# 05.net
KiCad netlist of a schematic drawn in Altium Designer
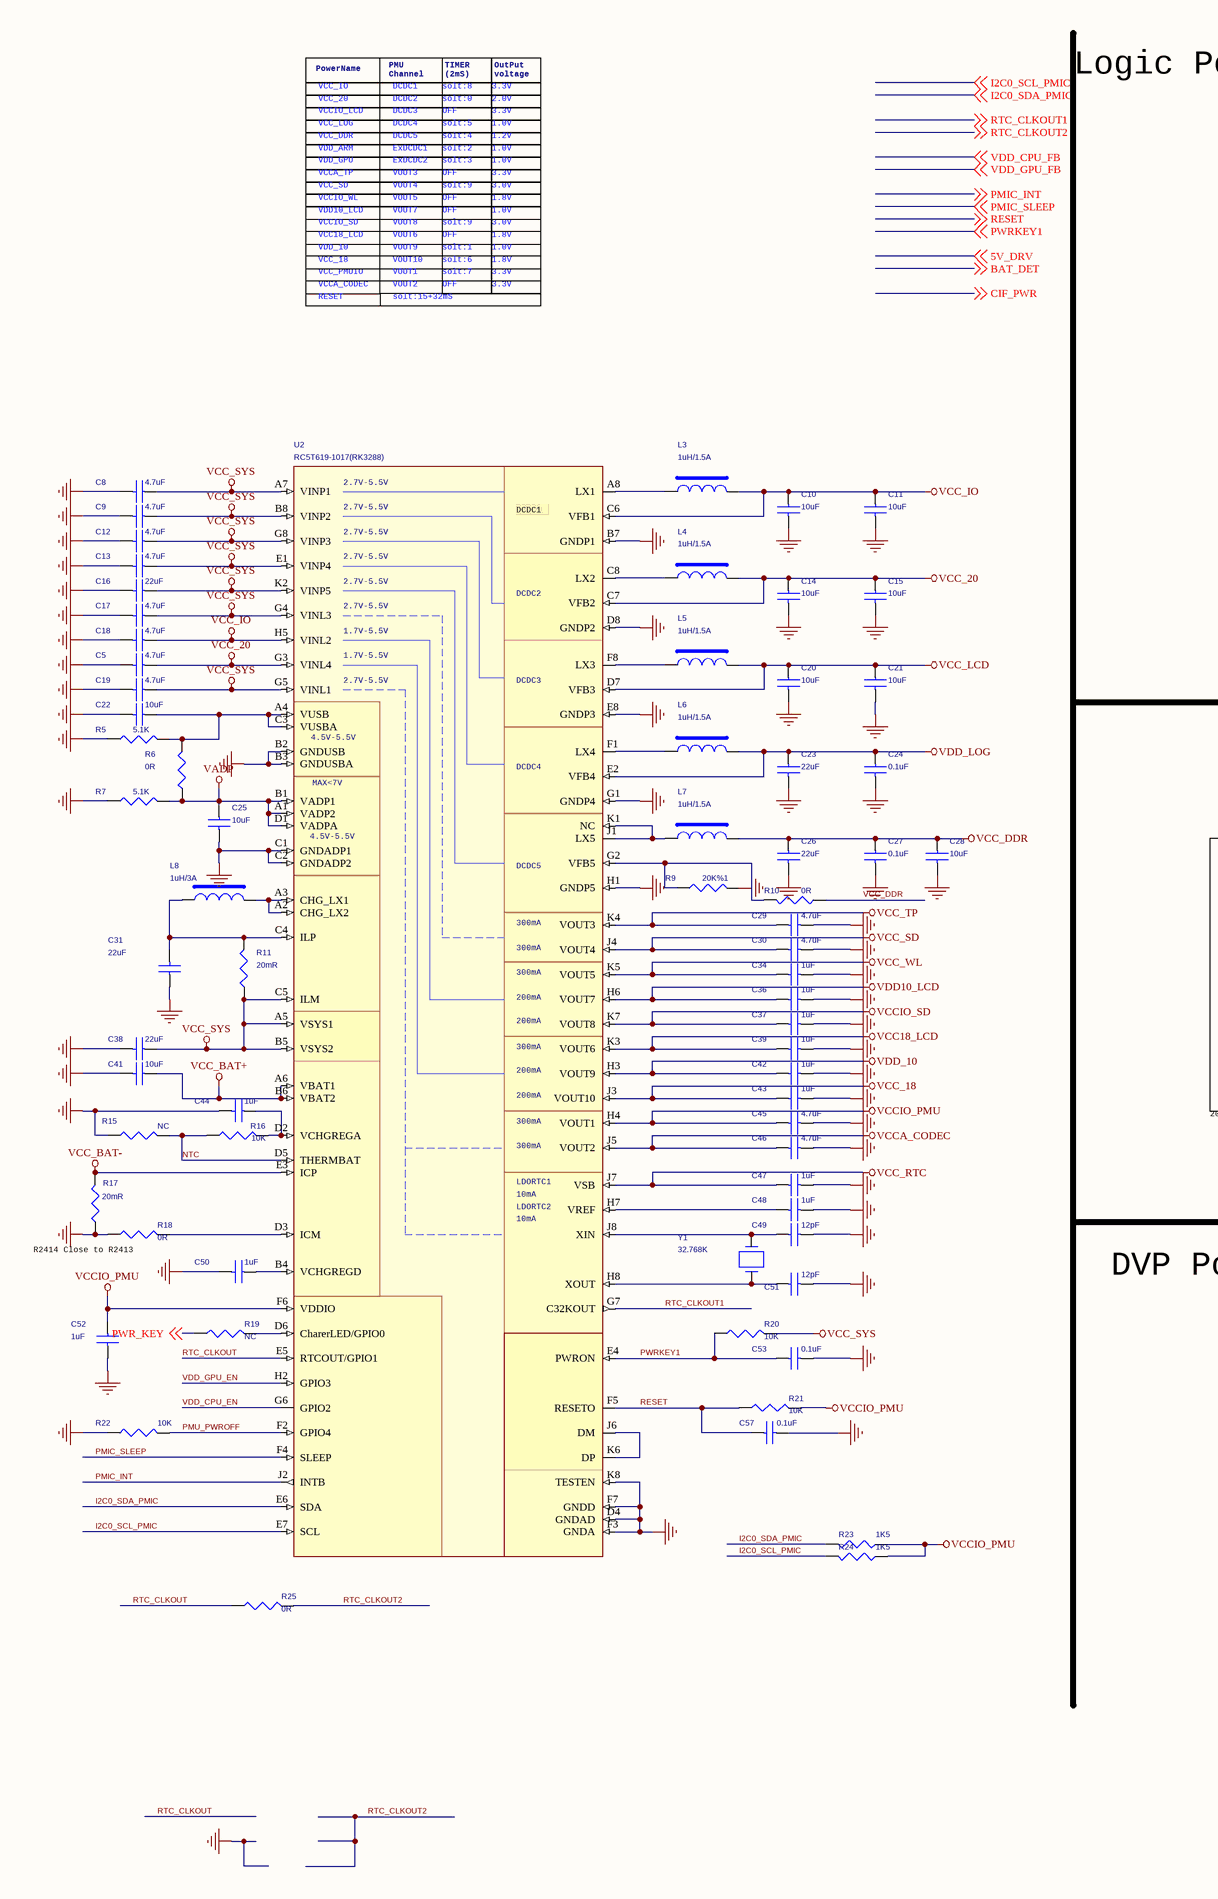
[diagram p0: 05.SchDoc, left]
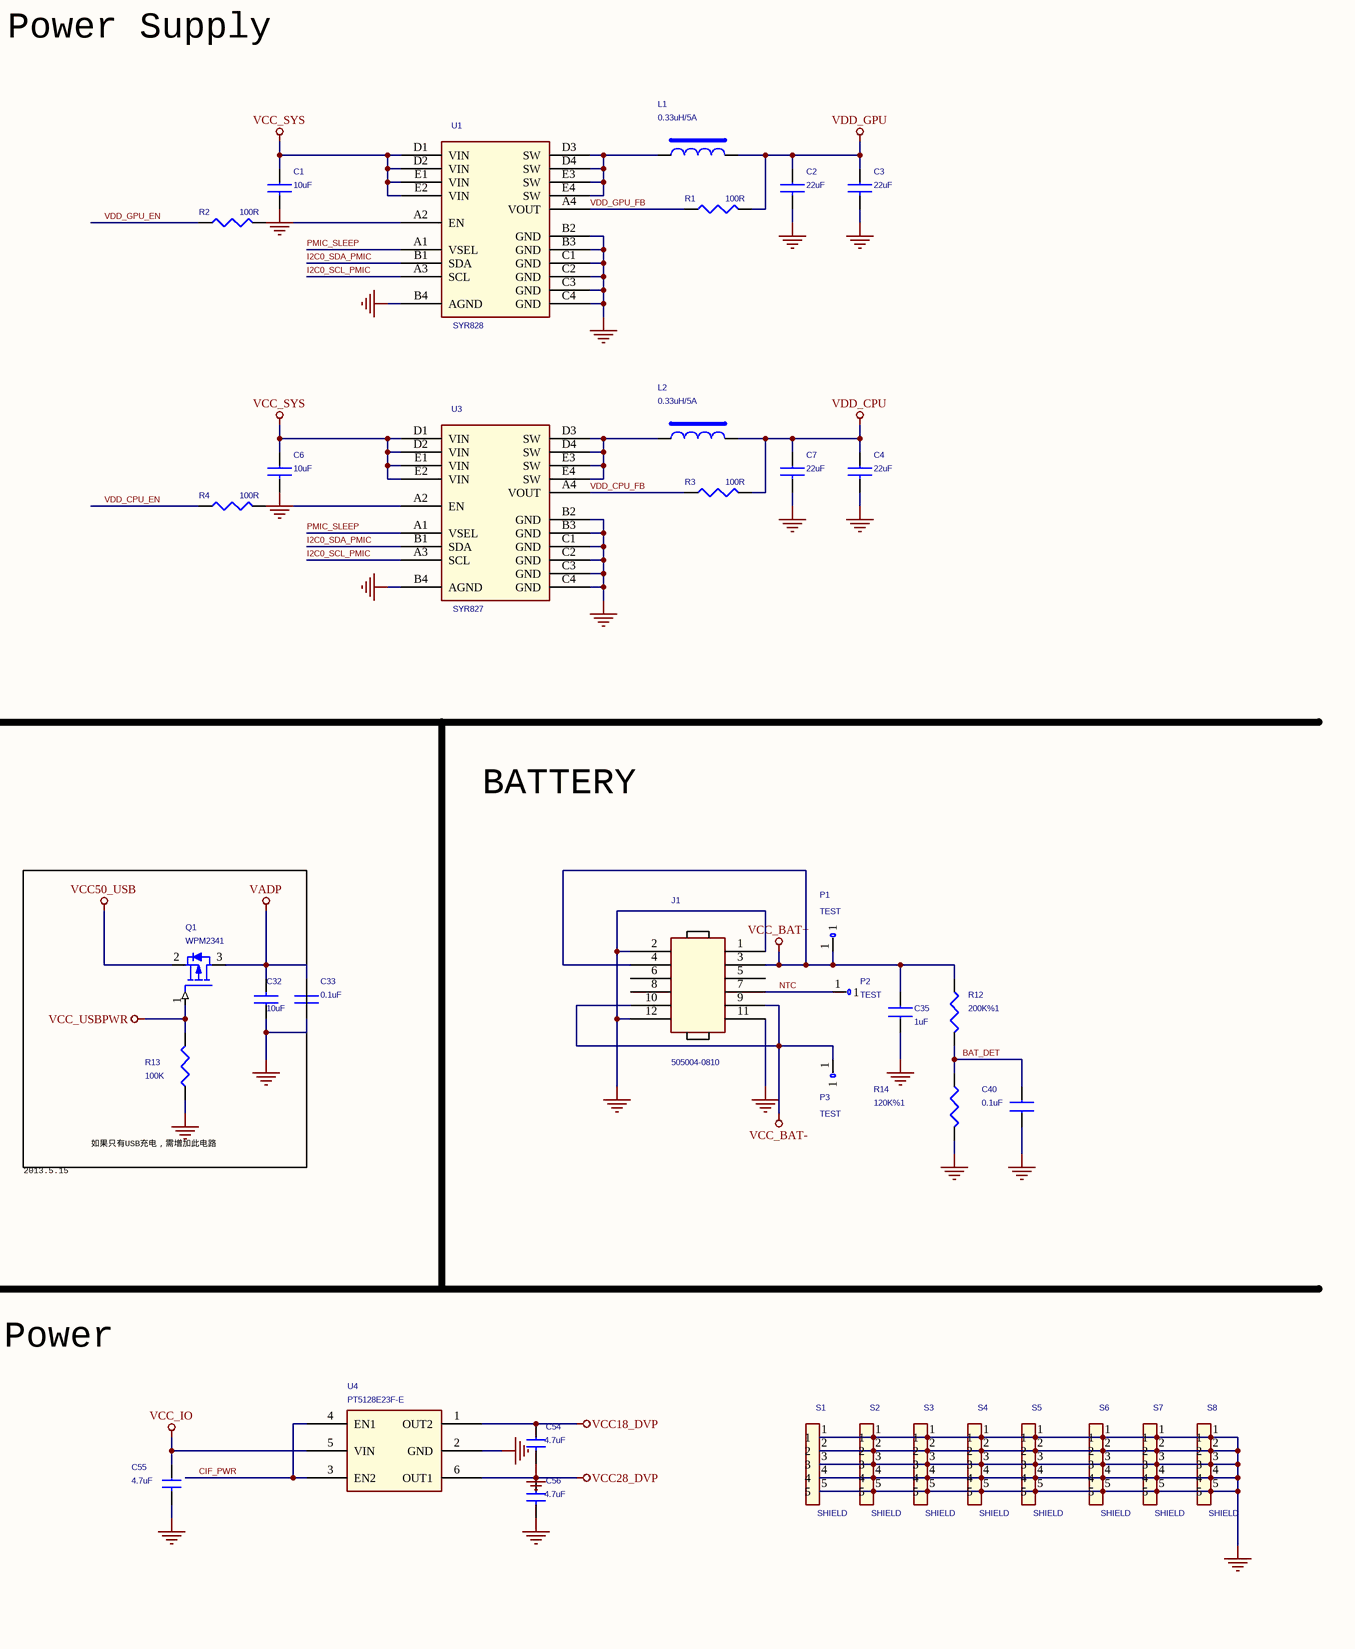
[diagram p1: 05.SchDoc, right]

(export (version "E")
  (design (tool "Eeschema 10.0.6"))
  (components
    (comp (ref "C1") (value "10uF") (footprint "C0603") (libsource (lib "*") (part "CAP NP_4")))
    (comp (ref "C2") (value "22uF") (footprint "C0805") (libsource (lib "*") (part "CAP NP_4")))
    (comp (ref "C3") (value "22uF") (footprint "C0805") (libsource (lib "*") (part "CAP NP_4")))
    (comp (ref "C4") (value "22uF") (footprint "C0805") (libsource (lib "*") (part "CAP NP_4")))
    (comp (ref "C5") (value "4.7uF") (footprint "C0603") (libsource (lib "*") (part "CAP NP_2")))
    (comp (ref "C6") (value "10uF") (footprint "C0603") (libsource (lib "*") (part "CAP NP_4")))
    (comp (ref "C7") (value "22uF") (footprint "C0805") (libsource (lib "*") (part "CAP NP_4")))
    (comp (ref "C8") (value "4.7uF") (footprint "C0603") (libsource (lib "*") (part "CAP NP_2")))
    (comp (ref "C9") (value "4.7uF") (footprint "C0603") (libsource (lib "*") (part "CAP NP_2")))
    (comp (ref "C10") (value "10uF") (footprint "C0603") (libsource (lib "*") (part "CAP NP_2")))
    (comp (ref "C11") (value "10uF") (footprint "C0603") (libsource (lib "*") (part "CAP NP_2")))
    (comp (ref "C12") (value "4.7uF") (footprint "C0603") (libsource (lib "*") (part "CAP NP_2")))
    (comp (ref "C13") (value "4.7uF") (footprint "C0603") (libsource (lib "*") (part "CAP NP_2")))
    (comp (ref "C14") (value "10uF") (footprint "C0603") (libsource (lib "*") (part "CAP NP_2")))
    (comp (ref "C15") (value "10uF") (footprint "C0603") (libsource (lib "*") (part "CAP NP_2")))
    (comp (ref "C16") (value "22uF") (footprint "C0805") (libsource (lib "*") (part "CAP NP_2")))
    (comp (ref "C17") (value "4.7uF") (footprint "C0603") (libsource (lib "*") (part "CAP NP_2")))
    (comp (ref "C18") (value "4.7uF") (footprint "C0603") (libsource (lib "*") (part "CAP NP_2")))
    (comp (ref "C19") (value "4.7uF") (footprint "C0603") (libsource (lib "*") (part "CAP NP_2")))
    (comp (ref "C20") (value "10uF") (footprint "C0603") (libsource (lib "*") (part "CAP NP_2")))
    (comp (ref "C21") (value "10uF") (footprint "C0603") (libsource (lib "*") (part "CAP NP_2")))
    (comp (ref "C22") (value "10uF") (footprint "C0603") (libsource (lib "*") (part "CAP NP_2")))
    (comp (ref "C23") (value "22uF") (footprint "C0805") (libsource (lib "*") (part "CAP NP_2")))
    (comp (ref "C24") (value "0.1uF") (footprint "c0402") (libsource (lib "*") (part "CAP NP_2")))
    (comp (ref "C25") (value "10uF") (footprint "C0603") (libsource (lib "*") (part "CAP NP_2")))
    (comp (ref "C26") (value "22uF") (footprint "C0805") (libsource (lib "*") (part "CAP NP_2")))
    (comp (ref "C27") (value "0.1uF") (footprint "c0402") (libsource (lib "*") (part "CAP NP_2")))
    (comp (ref "C28") (value "10uF") (footprint "C0603") (libsource (lib "*") (part "CAP NP_2")))
    (comp (ref "C29") (value "4.7uF") (footprint "C0603") (libsource (lib "*") (part "CAP NP_2")))
    (comp (ref "C30") (value "4.7uF") (footprint "C0603") (libsource (lib "*") (part "CAP NP_2")))
    (comp (ref "C31") (value "22uF") (footprint "C0805") (libsource (lib "*") (part "CAP NP_2")))
    (comp (ref "C32")
      (value "10uF")
      (footprint "C0603")
      (description "RoHS CHIP CAP 10uF +10/-10% X5R")
      (libsource (lib "*") (part "CAP NP_1"))
    )
    (comp (ref "C33")
      (value "0.1uF")
      (footprint "C0402")
      (description "RoHS CHIP CAP 0.1uF +10/-10% X7R")
      (libsource (lib "*") (part "CAP NP_Dup2"))
    )
    (comp (ref "C34") (value "1uF") (footprint "c0402") (libsource (lib "*") (part "CAP NP_2")))
    (comp (ref "C35")
      (value "1uF")
      (footprint "C0603")
      (description "RoHS CHIP CAP 1uF +10/-10% 16V X5R")
      (libsource (lib "*") (part "CAP NP_Dup3"))
    )
    (comp (ref "C36") (value "1uF") (footprint "c0402") (libsource (lib "*") (part "CAP NP_2")))
    (comp (ref "C37") (value "1uF") (footprint "c0402") (libsource (lib "*") (part "CAP NP_2")))
    (comp (ref "C38") (value "22uF") (footprint "C0805") (libsource (lib "*") (part "CAP NP_2")))
    (comp (ref "C39") (value "1uF") (footprint "c0402") (libsource (lib "*") (part "CAP NP_2")))
    (comp (ref "C40")
      (value "0.1uF")
      (footprint "C0603")
      (description "RoHS CHIP CAP 0.1uF +10/-10% X7R")
      (libsource (lib "*") (part "CAP NP_Dup3"))
    )
    (comp (ref "C41") (value "10uF") (footprint "C0603") (libsource (lib "*") (part "CAP NP_2")))
    (comp (ref "C42") (value "1uF") (footprint "c0402") (libsource (lib "*") (part "CAP NP_2")))
    (comp (ref "C43") (value "1uF") (footprint "c0402") (libsource (lib "*") (part "CAP NP_2")))
    (comp (ref "C44") (value "1uF") (footprint "c0402") (libsource (lib "*") (part "CAP NP_2")))
    (comp (ref "C45") (value "4.7uF") (footprint "C0603") (libsource (lib "*") (part "CAP NP_2")))
    (comp (ref "C46") (value "4.7uF") (footprint "C0603") (libsource (lib "*") (part "CAP NP_2")))
    (comp (ref "C47") (value "1uF") (footprint "c0402") (libsource (lib "*") (part "CAP NP_2")))
    (comp (ref "C48") (value "1uF") (footprint "c0402") (libsource (lib "*") (part "CAP NP_2")))
    (comp (ref "C49") (value "12pF") (footprint "c0402") (libsource (lib "*") (part "CAP NP_4")))
    (comp (ref "C50") (value "1uF") (footprint "c0402") (libsource (lib "*") (part "CAP NP_2")))
    (comp (ref "C51") (value "12pF") (footprint "c0402") (libsource (lib "*") (part "CAP NP_4")))
    (comp (ref "C52") (value "1uF") (footprint "c0402") (libsource (lib "*") (part "CAP NP_2")))
    (comp (ref "C53") (value "0.1uF") (footprint "c0402") (libsource (lib "*") (part "CAP NP_2")))
    (comp (ref "C54")
      (value "4.7uF")
      (footprint "C0603")
      (description "贴片电容")
      (libsource (lib "*") (part "SMALL CAP"))
    )
    (comp (ref "C55")
      (value "4.7uF")
      (footprint "C0603")
      (description "贴片电容")
      (libsource (lib "*") (part "SMALL CAP"))
    )
    (comp (ref "C56")
      (value "4.7uF")
      (footprint "C0603")
      (description "贴片电容")
      (libsource (lib "*") (part "SMALL CAP"))
    )
    (comp (ref "C57") (value "0.1uF") (footprint "c0402") (libsource (lib "*") (part "CAP NP_2")))
    (comp (ref "J1")
      (value "505004-0810")
      (footprint "505004-0810")
      (libsource (lib "*") (part "HEADER 6X2"))
    )
    (comp (ref "L1")
      (value "0.33uH/5A")
      (footprint "IND-4X4")
      (libsource (lib "*") (part "INDUCTORS OF FERRITE_Dup1"))
    )
    (comp (ref "L2")
      (value "0.33uH/5A")
      (footprint "IND-4X4")
      (libsource (lib "*") (part "INDUCTORS OF FERRITE_Dup1"))
    )
    (comp (ref "L3")
      (value "1uH/1.5A")
      (footprint "IND-3X3")
      (libsource (lib "*") (part "INDUCTORS OF FERRITE_Dup1"))
    )
    (comp (ref "L4")
      (value "1uH/1.5A")
      (footprint "IND-3X3")
      (libsource (lib "*") (part "INDUCTORS OF FERRITE_Dup1"))
    )
    (comp (ref "L5")
      (value "1uH/1.5A")
      (footprint "IND-3X3")
      (libsource (lib "*") (part "INDUCTORS OF FERRITE_Dup1"))
    )
    (comp (ref "L6")
      (value "1uH/1.5A")
      (footprint "IND-3X3")
      (libsource (lib "*") (part "INDUCTORS OF FERRITE_Dup1"))
    )
    (comp (ref "L7")
      (value "1uH/1.5A")
      (footprint "IND-3X3")
      (libsource (lib "*") (part "INDUCTORS OF FERRITE_Dup1"))
    )
    (comp (ref "L8")
      (value "1uH/3A")
      (footprint "IND-5X5")
      (libsource (lib "*") (part "INDUCTORS OF FERRITE_Dup1"))
    )
    (comp (ref "P1") (value "TEST") (footprint "TEST") (libsource (lib "*") (part "TEST_0")))
    (comp (ref "P2") (value "TEST") (footprint "TEST") (libsource (lib "*") (part "TEST_0")))
    (comp (ref "P3") (value "TEST") (footprint "TEST") (libsource (lib "*") (part "TEST_0")))
    (comp (ref "Q1")
      (value "WPM2341")
      (footprint "SOT23")
      (description "MOSFET-P,WPM2341 ,-20V,+/-8V,-2.8A,56m Ohm@Vgs=-2.5V,44m Ohm@Vgs=-4.5V,SOT23")
      (libsource (lib "*") (part "MOSFET P"))
    )
    (comp (ref "R1")
      (value "100R")
      (footprint "r0402")
      (description "RES,thick film,47KOhm,+/-5%,1/16W,SMD0402")
      (libsource (lib "*") (part "RESISTOR_1_Dup2"))
    )
    (comp (ref "R2")
      (value "100R")
      (footprint "r0402")
      (description "RES,thick film,47KOhm,+/-5%,1/16W,SMD0402")
      (libsource (lib "*") (part "RESISTOR_1_Dup2"))
    )
    (comp (ref "R3")
      (value "100R")
      (footprint "r0402")
      (description "RES,thick film,47KOhm,+/-5%,1/16W,SMD0402")
      (libsource (lib "*") (part "RESISTOR_1_Dup2"))
    )
    (comp (ref "R4")
      (value "100R")
      (footprint "r0402")
      (description "RES,thick film,47KOhm,+/-5%,1/16W,SMD0402")
      (libsource (lib "*") (part "RESISTOR_1_Dup2"))
    )
    (comp (ref "R5")
      (value "5.1K")
      (footprint "r0402")
      (description "贴片电阻")
      (libsource (lib "*") (part "RESISTOR_1"))
    )
    (comp (ref "R6")
      (value "0R")
      (footprint "R0402")
      (description "贴片电阻")
      (libsource (lib "*") (part "RESISTOR_1"))
    )
    (comp (ref "R7")
      (value "5.1K")
      (footprint "r0402")
      (description "贴片电阻")
      (libsource (lib "*") (part "RESISTOR_1"))
    )
    (comp (ref "R9")
      (value "20K%1")
      (footprint "r0402")
      (description "贴片电阻")
      (libsource (lib "*") (part "RESISTOR_1"))
    )
    (comp (ref "R10")
      (value "0R")
      (footprint "r0402")
      (description "贴片电阻")
      (libsource (lib "*") (part "RESISTOR_1"))
    )
    (comp (ref "R11")
      (value "20mR")
      (footprint "R1210")
      (description "贴片电阻")
      (libsource (lib "*") (part "RESISTOR_1"))
    )
    (comp (ref "R12")
      (value "200K%1")
      (footprint "r0402")
      (description "ROHS CHIP RES 100K 1/16W 1%")
      (libsource (lib "*") (part "RES 1B_Dup1"))
    )
    (comp (ref "R13")
      (value "100K")
      (footprint "r0402")
      (description "ROHS CHIP RES 10K 1/16W +/-5%")
      (libsource (lib "*") (part "RESISTOR"))
    )
    (comp (ref "R14")
      (value "120K%1")
      (footprint "r0402")
      (description "ROHS CHIP RES 100K 1/16W 1%")
      (libsource (lib "*") (part "RES 1B_Dup1"))
    )
    (comp (ref "R15")
      (value "NC")
      (footprint "r0402")
      (description "贴片电阻")
      (libsource (lib "*") (part "RESISTOR_1"))
    )
    (comp (ref "R16")
      (value "10K")
      (footprint "r0402")
      (description "贴片电阻")
      (libsource (lib "*") (part "RESISTOR_1"))
    )
    (comp (ref "R17")
      (value "20mR")
      (footprint "R1210")
      (description "贴片电阻")
      (libsource (lib "*") (part "RESISTOR_1"))
    )
    (comp (ref "R18")
      (value "0R")
      (footprint "r0402")
      (description "贴片电阻")
      (libsource (lib "*") (part "RESISTOR_1"))
    )
    (comp (ref "R19")
      (value "NC")
      (footprint "r0402")
      (description "贴片电阻")
      (libsource (lib "*") (part "RESISTOR_1"))
    )
    (comp (ref "R20")
      (value "10K")
      (footprint "r0402")
      (description "贴片电阻")
      (libsource (lib "*") (part "RESISTOR_1"))
    )
    (comp (ref "R21")
      (value "10K")
      (footprint "r0402")
      (description "贴片电阻")
      (libsource (lib "*") (part "RESISTOR_1"))
    )
    (comp (ref "R22")
      (value "10K")
      (footprint "r0402")
      (description "贴片电阻")
      (libsource (lib "*") (part "RESISTOR_1"))
    )
    (comp (ref "R23")
      (value "1K5")
      (footprint "r0402")
      (description "RES,thick film,47KOhm,+/-5%,1/16W,SMD0402")
      (libsource (lib "*") (part "RESISTOR_1_Dup2"))
    )
    (comp (ref "R24")
      (value "1K5")
      (footprint "r0402")
      (description "RES,thick film,47KOhm,+/-5%,1/16W,SMD0402")
      (libsource (lib "*") (part "RESISTOR_1_Dup2"))
    )
    (comp (ref "R25")
      (value "0R")
      (footprint "r0402")
      (description "贴片电阻")
      (libsource (lib "*") (part "RESISTOR_1"))
    )
    (comp (ref "S1") (value "SHIELD") (footprint "0_9MM_SHIELD") (libsource (lib "*") (part "SHIELD")))
    (comp (ref "S2") (value "SHIELD") (footprint "0_9MM_SHIELD") (libsource (lib "*") (part "SHIELD")))
    (comp (ref "S3") (value "SHIELD") (footprint "0_9MM_SHIELD") (libsource (lib "*") (part "SHIELD")))
    (comp (ref "S4") (value "SHIELD") (footprint "0_9MM_SHIELD") (libsource (lib "*") (part "SHIELD")))
    (comp (ref "S5") (value "SHIELD") (footprint "0_9MM_SHIELD") (libsource (lib "*") (part "SHIELD")))
    (comp (ref "S6") (value "SHIELD") (footprint "0_9MM_SHIELD") (libsource (lib "*") (part "SHIELD")))
    (comp (ref "S7") (value "SHIELD") (footprint "0_9MM_SHIELD") (libsource (lib "*") (part "SHIELD")))
    (comp (ref "S8") (value "SHIELD") (footprint "0_9MM_SHIELD") (libsource (lib "*") (part "SHIELD")))
    (comp (ref "U1") (value "SYR828") (footprint "WLCSP-20") (libsource (lib "*") (part "BB27_1")))
    (comp (ref "U2")
      (value "RC5T619-1017(RK3288)")
      (footprint "CSP0608-80")
      (libsource (lib "*") (part "5T619_2"))
    )
    (comp (ref "U3") (value "SYR827") (footprint "WLCSP-20") (libsource (lib "*") (part "BB27_1")))
    (comp (ref "U4") (value "PT5128E23F-E") (footprint "SOT26") (libsource (lib "*") (part "PT5127")))
    (comp (ref "Y1")
      (value "32.768K")
      (footprint "CRY-MC146")
      (description "Crystal,32.768KHz,+/-30ppm,12pF,MC146,-10°C ~ +60   °C")
      (libsource (lib "*") (part "CRYSTAL"))
    )
  )
  (nets
    (net (code "1") (name "/NTC") (class "Default")
      (node (ref "J1") (pin "7") (pinfunction "7_7") (pintype "passive"))
      (node (ref "P2") (pin "1") (pinfunction "1_1") (pintype "passive"))
      (node (ref "R15") (pin "1") (pinfunction "1_1") (pintype "passive"))
      (node (ref "R16") (pin "2") (pinfunction "2_2") (pintype "passive"))
      (node (ref "U2") (pin "D5") (pinfunction "THERMBAT_D5") (pintype "input"))
    )
    (net (code "2") (name "/PMU_PWROFF") (class "Default")
      (node (ref "R22") (pin "2") (pinfunction "2_2") (pintype "passive"))
      (node (ref "U2") (pin "F2") (pinfunction "GPIO4_F2") (pintype "input"))
    )
    (net (code "3") (name "/RTC_CLKOUT") (class "Default")
      (node (ref "R25") (pin "2") (pinfunction "2_2") (pintype "passive"))
      (node (ref "U2") (pin "E5") (pinfunction "RTCOUT/GPIO1_E5") (pintype "input"))
    )
    (net (code "4") (name "/VDD_CPU_EN") (class "Default")
      (node (ref "R4") (pin "2") (pinfunction "2_2") (pintype "passive"))
      (node (ref "U2") (pin "G6") (pinfunction "GPIO2_G6") (pintype "passive"))
    )
    (net (code "5") (name "/VDD_GPU_EN") (class "Default")
      (node (ref "R2") (pin "2") (pinfunction "2_2") (pintype "passive"))
      (node (ref "U2") (pin "H2") (pinfunction "GPIO3_H2") (pintype "input"))
    )
    (net (code "7") (name "BAT_DET") (class "Default")
      (node (ref "C40") (pin "2") (pinfunction "2_2") (pintype "passive"))
      (node (ref "R12") (pin "1") (pinfunction "1_1") (pintype "passive"))
      (node (ref "R14") (pin "2") (pinfunction "2_2") (pintype "passive"))
    )
    (net (code "8") (name "CIF_PWR") (class "Default")
      (node (ref "U4") (pin "3") (pinfunction "EN2_3") (pintype "passive"))
      (node (ref "U4") (pin "4") (pinfunction "EN1_4") (pintype "passive"))
    )
    (net (code "9") (name "GND") (class "Default")
      (node (ref "C1") (pin "2") (pinfunction "2_2") (pintype "passive"))
      (node (ref "C10") (pin "2") (pinfunction "2_2") (pintype "passive"))
      (node (ref "C11") (pin "2") (pinfunction "2_2") (pintype "passive"))
      (node (ref "C12") (pin "2") (pinfunction "2_2") (pintype "passive"))
      (node (ref "C13") (pin "2") (pinfunction "2_2") (pintype "passive"))
      (node (ref "C14") (pin "2") (pinfunction "2_2") (pintype "passive"))
      (node (ref "C15") (pin "2") (pinfunction "2_2") (pintype "passive"))
      (node (ref "C16") (pin "2") (pinfunction "2_2") (pintype "passive"))
      (node (ref "C17") (pin "2") (pinfunction "2_2") (pintype "passive"))
      (node (ref "C18") (pin "2") (pinfunction "2_2") (pintype "passive"))
      (node (ref "C19") (pin "2") (pinfunction "2_2") (pintype "passive"))
      (node (ref "C2") (pin "2") (pinfunction "2_2") (pintype "passive"))
      (node (ref "C20") (pin "2") (pinfunction "2_2") (pintype "passive"))
      (node (ref "C21") (pin "2") (pinfunction "2_2") (pintype "passive"))
      (node (ref "C22") (pin "2") (pinfunction "2_2") (pintype "passive"))
      (node (ref "C23") (pin "2") (pinfunction "2_2") (pintype "passive"))
      (node (ref "C24") (pin "2") (pinfunction "2_2") (pintype "passive"))
      (node (ref "C25") (pin "2") (pinfunction "2_2") (pintype "passive"))
      (node (ref "C26") (pin "2") (pinfunction "2_2") (pintype "passive"))
      (node (ref "C27") (pin "2") (pinfunction "2_2") (pintype "passive"))
      (node (ref "C28") (pin "2") (pinfunction "2_2") (pintype "passive"))
      (node (ref "C29") (pin "2") (pinfunction "2_2") (pintype "passive"))
      (node (ref "C3") (pin "2") (pinfunction "2_2") (pintype "passive"))
      (node (ref "C30") (pin "2") (pinfunction "2_2") (pintype "passive"))
      (node (ref "C31") (pin "1") (pinfunction "1_1") (pintype "passive"))
      (node (ref "C32") (pin "1") (pinfunction "1_1") (pintype "passive"))
      (node (ref "C33") (pin "1") (pinfunction "1_1") (pintype "passive"))
      (node (ref "C34") (pin "2") (pinfunction "2_2") (pintype "passive"))
      (node (ref "C35") (pin "1") (pinfunction "1_1") (pintype "passive"))
      (node (ref "C36") (pin "2") (pinfunction "2_2") (pintype "passive"))
      (node (ref "C37") (pin "2") (pinfunction "2_2") (pintype "passive"))
      (node (ref "C38") (pin "2") (pinfunction "2_2") (pintype "passive"))
      (node (ref "C39") (pin "2") (pinfunction "2_2") (pintype "passive"))
      (node (ref "C4") (pin "2") (pinfunction "2_2") (pintype "passive"))
      (node (ref "C40") (pin "1") (pinfunction "1_1") (pintype "passive"))
      (node (ref "C41") (pin "2") (pinfunction "2_2") (pintype "passive"))
      (node (ref "C42") (pin "2") (pinfunction "2_2") (pintype "passive"))
      (node (ref "C43") (pin "2") (pinfunction "2_2") (pintype "passive"))
      (node (ref "C44") (pin "2") (pinfunction "2_2") (pintype "passive"))
      (node (ref "C45") (pin "2") (pinfunction "2_2") (pintype "passive"))
      (node (ref "C46") (pin "2") (pinfunction "2_2") (pintype "passive"))
      (node (ref "C47") (pin "2") (pinfunction "2_2") (pintype "passive"))
      (node (ref "C48") (pin "2") (pinfunction "2_2") (pintype "passive"))
      (node (ref "C49") (pin "2") (pinfunction "2_2") (pintype "passive"))
      (node (ref "C5") (pin "2") (pinfunction "2_2") (pintype "passive"))
      (node (ref "C50") (pin "2") (pinfunction "2_2") (pintype "passive"))
      (node (ref "C51") (pin "2") (pinfunction "2_2") (pintype "passive"))
      (node (ref "C52") (pin "2") (pinfunction "2_2") (pintype "passive"))
      (node (ref "C53") (pin "2") (pinfunction "2_2") (pintype "passive"))
      (node (ref "C54") (pin "2") (pinfunction "2_2") (pintype "passive"))
      (node (ref "C55") (pin "2") (pinfunction "2_2") (pintype "passive"))
      (node (ref "C56") (pin "2") (pinfunction "2_2") (pintype "passive"))
      (node (ref "C57") (pin "2") (pinfunction "2_2") (pintype "passive"))
      (node (ref "C6") (pin "2") (pinfunction "2_2") (pintype "passive"))
      (node (ref "C7") (pin "2") (pinfunction "2_2") (pintype "passive"))
      (node (ref "C8") (pin "2") (pinfunction "2_2") (pintype "passive"))
      (node (ref "C9") (pin "2") (pinfunction "2_2") (pintype "passive"))
      (node (ref "J1") (pin "1") (pinfunction "1_1") (pintype "passive"))
      (node (ref "J1") (pin "11") (pinfunction "11_11") (pintype "passive"))
      (node (ref "J1") (pin "12") (pinfunction "12_12") (pintype "passive"))
      (node (ref "J1") (pin "2") (pinfunction "2_2") (pintype "passive"))
      (node (ref "R13") (pin "1") (pinfunction "1_1") (pintype "passive"))
      (node (ref "R14") (pin "1") (pinfunction "1_1") (pintype "passive"))
      (node (ref "R15") (pin "2") (pinfunction "2_2") (pintype "passive"))
      (node (ref "R17") (pin "1") (pinfunction "1_1") (pintype "passive"))
      (node (ref "R18") (pin "2") (pinfunction "2_2") (pintype "passive"))
      (node (ref "R22") (pin "1") (pinfunction "1_1") (pintype "passive"))
      (node (ref "R5") (pin "1") (pinfunction "1_1") (pintype "passive"))
      (node (ref "R7") (pin "1") (pinfunction "1_1") (pintype "passive"))
      (node (ref "R9") (pin "2") (pinfunction "2_2") (pintype "passive"))
      (node (ref "S1") (pin "1") (pinfunction "1_1") (pintype "passive"))
      (node (ref "S1") (pin "2") (pinfunction "2_2") (pintype "passive"))
      (node (ref "S1") (pin "3") (pinfunction "3_3") (pintype "passive"))
      (node (ref "S1") (pin "4") (pinfunction "4_4") (pintype "passive"))
      (node (ref "S1") (pin "5") (pinfunction "5_5") (pintype "passive"))
      (node (ref "S2") (pin "1") (pinfunction "1_1") (pintype "passive"))
      (node (ref "S2") (pin "2") (pinfunction "2_2") (pintype "passive"))
      (node (ref "S2") (pin "3") (pinfunction "3_3") (pintype "passive"))
      (node (ref "S2") (pin "4") (pinfunction "4_4") (pintype "passive"))
      (node (ref "S2") (pin "5") (pinfunction "5_5") (pintype "passive"))
      (node (ref "S3") (pin "1") (pinfunction "1_1") (pintype "passive"))
      (node (ref "S3") (pin "2") (pinfunction "2_2") (pintype "passive"))
      (node (ref "S3") (pin "3") (pinfunction "3_3") (pintype "passive"))
      (node (ref "S3") (pin "4") (pinfunction "4_4") (pintype "passive"))
      (node (ref "S3") (pin "5") (pinfunction "5_5") (pintype "passive"))
      (node (ref "S4") (pin "1") (pinfunction "1_1") (pintype "passive"))
      (node (ref "S4") (pin "2") (pinfunction "2_2") (pintype "passive"))
      (node (ref "S4") (pin "3") (pinfunction "3_3") (pintype "passive"))
      (node (ref "S4") (pin "4") (pinfunction "4_4") (pintype "passive"))
      (node (ref "S4") (pin "5") (pinfunction "5_5") (pintype "passive"))
      (node (ref "S5") (pin "1") (pinfunction "1_1") (pintype "passive"))
      (node (ref "S5") (pin "2") (pinfunction "2_2") (pintype "passive"))
      (node (ref "S5") (pin "3") (pinfunction "3_3") (pintype "passive"))
      (node (ref "S5") (pin "4") (pinfunction "4_4") (pintype "passive"))
      (node (ref "S5") (pin "5") (pinfunction "5_5") (pintype "passive"))
      (node (ref "S6") (pin "1") (pinfunction "1_1") (pintype "passive"))
      (node (ref "S6") (pin "2") (pinfunction "2_2") (pintype "passive"))
      (node (ref "S6") (pin "3") (pinfunction "3_3") (pintype "passive"))
      (node (ref "S6") (pin "4") (pinfunction "4_4") (pintype "passive"))
      (node (ref "S6") (pin "5") (pinfunction "5_5") (pintype "passive"))
      (node (ref "S7") (pin "1") (pinfunction "1_1") (pintype "passive"))
      (node (ref "S7") (pin "2") (pinfunction "2_2") (pintype "passive"))
      (node (ref "S7") (pin "3") (pinfunction "3_3") (pintype "passive"))
      (node (ref "S7") (pin "4") (pinfunction "4_4") (pintype "passive"))
      (node (ref "S7") (pin "5") (pinfunction "5_5") (pintype "passive"))
      (node (ref "S8") (pin "1") (pinfunction "1_1") (pintype "passive"))
      (node (ref "S8") (pin "2") (pinfunction "2_2") (pintype "passive"))
      (node (ref "S8") (pin "3") (pinfunction "3_3") (pintype "passive"))
      (node (ref "S8") (pin "4") (pinfunction "4_4") (pintype "passive"))
      (node (ref "S8") (pin "5") (pinfunction "5_5") (pintype "passive"))
      (node (ref "U1") (pin "B2") (pinfunction "GND_B2") (pintype "power_in"))
      (node (ref "U1") (pin "B3") (pinfunction "GND_B3") (pintype "power_in"))
      (node (ref "U1") (pin "B4") (pinfunction "AGND_B4") (pintype "passive"))
      (node (ref "U1") (pin "C1") (pinfunction "GND_C1") (pintype "power_in"))
      (node (ref "U1") (pin "C2") (pinfunction "GND_C2") (pintype "power_in"))
      (node (ref "U1") (pin "C3") (pinfunction "GND_C3") (pintype "power_in"))
      (node (ref "U1") (pin "C4") (pinfunction "GND_C4") (pintype "power_in"))
      (node (ref "U2") (pin "B2") (pinfunction "GNDUSB_B2") (pintype "input"))
      (node (ref "U2") (pin "B3") (pinfunction "GNDUSBA_B3") (pintype "input"))
      (node (ref "U2") (pin "B7") (pinfunction "GNDP1_B7") (pintype "input"))
      (node (ref "U2") (pin "C1") (pinfunction "GNDADP1_C1") (pintype "input"))
      (node (ref "U2") (pin "C2") (pinfunction "GNDADP2_C2") (pintype "input"))
      (node (ref "U2") (pin "D4") (pinfunction "GNDAD_D4") (pintype "input"))
      (node (ref "U2") (pin "D8") (pinfunction "GNDP2_D8") (pintype "input"))
      (node (ref "U2") (pin "E8") (pinfunction "GNDP3_E8") (pintype "input"))
      (node (ref "U2") (pin "F3") (pinfunction "GNDA_F3") (pintype "input"))
      (node (ref "U2") (pin "F7") (pinfunction "GNDD_F7") (pintype "input"))
      (node (ref "U2") (pin "G1") (pinfunction "GNDP4_G1") (pintype "input"))
      (node (ref "U2") (pin "H1") (pinfunction "GNDP5_H1") (pintype "input"))
      (node (ref "U2") (pin "K8") (pinfunction "TESTEN_K8") (pintype "input"))
      (node (ref "U3") (pin "B2") (pinfunction "GND_B2") (pintype "power_in"))
      (node (ref "U3") (pin "B3") (pinfunction "GND_B3") (pintype "power_in"))
      (node (ref "U3") (pin "B4") (pinfunction "AGND_B4") (pintype "passive"))
      (node (ref "U3") (pin "C1") (pinfunction "GND_C1") (pintype "power_in"))
      (node (ref "U3") (pin "C2") (pinfunction "GND_C2") (pintype "power_in"))
      (node (ref "U3") (pin "C3") (pinfunction "GND_C3") (pintype "power_in"))
      (node (ref "U3") (pin "C4") (pinfunction "GND_C4") (pintype "power_in"))
      (node (ref "U4") (pin "2") (pinfunction "GND_2") (pintype "passive"))
    )
    (net (code "10") (name "I2C0_SCL_PMIC") (class "Default")
      (node (ref "R24") (pin "1") (pinfunction "1_1") (pintype "passive"))
      (node (ref "U1") (pin "A3") (pinfunction "SCL_A3") (pintype "passive"))
      (node (ref "U2") (pin "E7") (pinfunction "SCL_E7") (pintype "input"))
      (node (ref "U3") (pin "A3") (pinfunction "SCL_A3") (pintype "passive"))
    )
    (net (code "11") (name "I2C0_SDA_PMIC") (class "Default")
      (node (ref "R23") (pin "1") (pinfunction "1_1") (pintype "passive"))
      (node (ref "U1") (pin "B1") (pinfunction "SDA_B1") (pintype "passive"))
      (node (ref "U2") (pin "E6") (pinfunction "SDA_E6") (pintype "input"))
      (node (ref "U3") (pin "B1") (pinfunction "SDA_B1") (pintype "passive"))
    )
    (net (code "12") (name "Net-(L1-Pad1)") (class "Default")
      (node (ref "L1") (pin "1") (pinfunction "1_1") (pintype "passive"))
      (node (ref "U1") (pin "D3") (pinfunction "SW_D3") (pintype "power_in"))
      (node (ref "U1") (pin "D4") (pinfunction "SW_D4") (pintype "power_in"))
      (node (ref "U1") (pin "E3") (pinfunction "SW_E3") (pintype "power_in"))
      (node (ref "U1") (pin "E4") (pinfunction "SW_E4") (pintype "power_in"))
    )
    (net (code "13") (name "Net-(L2-Pad1)") (class "Default")
      (node (ref "L2") (pin "1") (pinfunction "1_1") (pintype "passive"))
      (node (ref "U3") (pin "D3") (pinfunction "SW_D3") (pintype "power_in"))
      (node (ref "U3") (pin "D4") (pinfunction "SW_D4") (pintype "power_in"))
      (node (ref "U3") (pin "E3") (pinfunction "SW_E3") (pintype "power_in"))
      (node (ref "U3") (pin "E4") (pinfunction "SW_E4") (pintype "power_in"))
    )
    (net (code "14") (name "Net-(U1-EN)") (class "Default")
      (node (ref "R2") (pin "1") (pinfunction "1_1") (pintype "passive"))
      (node (ref "U1") (pin "A2") (pinfunction "EN_A2") (pintype "passive"))
    )
    (net (code "15") (name "Net-(U2-CHG_LX1)") (class "Default")
      (node (ref "L8") (pin "2") (pinfunction "2_2") (pintype "passive"))
      (node (ref "U2") (pin "A2") (pinfunction "CHG_LX2_A2") (pintype "input"))
      (node (ref "U2") (pin "A3") (pinfunction "CHG_LX1_A3") (pintype "input"))
    )
    (net (code "16") (name "Net-(U2-CharerLED{slash}GPIO0)") (class "Default")
      (node (ref "R19") (pin "2") (pinfunction "2_2") (pintype "passive"))
      (node (ref "U2") (pin "D6") (pinfunction "CharerLED/GPIO0_D6") (pintype "input"))
    )
    (net (code "17") (name "Net-(U2-DM)") (class "Default")
      (node (ref "U2") (pin "J6") (pinfunction "DM_J6") (pintype "passive"))
      (node (ref "U2") (pin "K6") (pinfunction "DP_K6") (pintype "passive"))
    )
    (net (code "18") (name "Net-(U2-ICM)") (class "Default")
      (node (ref "R18") (pin "1") (pinfunction "1_1") (pintype "passive"))
      (node (ref "U2") (pin "D3") (pinfunction "ICM_D3") (pintype "input"))
    )
    (net (code "19") (name "Net-(U2-ILP)") (class "Default")
      (node (ref "C31") (pin "2") (pinfunction "2_2") (pintype "passive"))
      (node (ref "L8") (pin "1") (pinfunction "1_1") (pintype "passive"))
      (node (ref "R11") (pin "2") (pinfunction "2_2") (pintype "passive"))
      (node (ref "U2") (pin "C4") (pinfunction "ILP_C4") (pintype "input"))
    )
    (net (code "20") (name "Net-(U2-LX1)") (class "Default")
      (node (ref "L3") (pin "1") (pinfunction "1_1") (pintype "passive"))
      (node (ref "U2") (pin "A8") (pinfunction "LX1_A8") (pintype "passive"))
    )
    (net (code "21") (name "Net-(U2-LX2)") (class "Default")
      (node (ref "L4") (pin "1") (pinfunction "1_1") (pintype "passive"))
      (node (ref "U2") (pin "C8") (pinfunction "LX2_C8") (pintype "passive"))
    )
    (net (code "22") (name "Net-(U2-LX3)") (class "Default")
      (node (ref "L5") (pin "1") (pinfunction "1_1") (pintype "passive"))
      (node (ref "U2") (pin "F8") (pinfunction "LX3_F8") (pintype "passive"))
    )
    (net (code "23") (name "Net-(U2-LX4)") (class "Default")
      (node (ref "L6") (pin "1") (pinfunction "1_1") (pintype "passive"))
      (node (ref "U2") (pin "F1") (pinfunction "LX4_F1") (pintype "passive"))
    )
    (net (code "24") (name "Net-(U2-LX5)") (class "Default")
      (node (ref "L7") (pin "1") (pinfunction "1_1") (pintype "passive"))
      (node (ref "U2") (pin "J1") (pinfunction "LX5_J1") (pintype "passive"))
      (node (ref "U2") (pin "K1") (pinfunction "NC_K1") (pintype "input"))
    )
    (net (code "25") (name "Net-(U2-VCHGREGA)") (class "Default")
      (node (ref "C44") (pin "1") (pinfunction "1_1") (pintype "passive"))
      (node (ref "R16") (pin "1") (pinfunction "1_1") (pintype "passive"))
      (node (ref "U2") (pin "D2") (pinfunction "VCHGREGA_D2") (pintype "input"))
    )
    (net (code "26") (name "Net-(U2-VCHGREGD)") (class "Default")
      (node (ref "C50") (pin "1") (pinfunction "1_1") (pintype "passive"))
      (node (ref "U2") (pin "B4") (pinfunction "VCHGREGD_B4") (pintype "input"))
    )
    (net (code "27") (name "Net-(U2-VFB5)") (class "Default")
      (node (ref "R10") (pin "2") (pinfunction "2_2") (pintype "passive"))
      (node (ref "R9") (pin "1") (pinfunction "1_1") (pintype "passive"))
      (node (ref "U2") (pin "G2") (pinfunction "VFB5_G2") (pintype "input"))
    )
    (net (code "28") (name "Net-(U2-VREF)") (class "Default")
      (node (ref "C48") (pin "1") (pinfunction "1_1") (pintype "passive"))
      (node (ref "U2") (pin "H7") (pinfunction "VREF_H7") (pintype "input"))
    )
    (net (code "29") (name "Net-(U2-VUSB)") (class "Default")
      (node (ref "C22") (pin "1") (pinfunction "1_1") (pintype "passive"))
      (node (ref "R5") (pin "2") (pinfunction "2_2") (pintype "passive"))
      (node (ref "R6") (pin "2") (pinfunction "2_2") (pintype "passive"))
      (node (ref "U2") (pin "A4") (pinfunction "VUSB_A4") (pintype "input"))
      (node (ref "U2") (pin "C3") (pinfunction "VUSBA_C3") (pintype "input"))
    )
    (net (code "30") (name "Net-(U2-XIN)") (class "Default")
      (node (ref "C49") (pin "1") (pinfunction "1_1") (pintype "passive"))
      (node (ref "U2") (pin "J8") (pinfunction "XIN_J8") (pintype "input"))
      (node (ref "Y1") (pin "1") (pinfunction "1_1") (pintype "passive"))
    )
    (net (code "31") (name "Net-(U2-XOUT)") (class "Default")
      (node (ref "C51") (pin "1") (pinfunction "1_1") (pintype "passive"))
      (node (ref "U2") (pin "H8") (pinfunction "XOUT_H8") (pintype "input"))
      (node (ref "Y1") (pin "2") (pinfunction "2_2") (pintype "passive"))
    )
    (net (code "32") (name "Net-(U3-EN)") (class "Default")
      (node (ref "R4") (pin "1") (pinfunction "1_1") (pintype "passive"))
      (node (ref "U3") (pin "A2") (pinfunction "EN_A2") (pintype "passive"))
    )
    (net (code "33") (name "PMIC_INT") (class "Default")
      (node (ref "U2") (pin "J2") (pinfunction "INTB_J2") (pintype "output"))
    )
    (net (code "34") (name "PMIC_SLEEP") (class "Default")
      (node (ref "U1") (pin "A1") (pinfunction "VSEL_A1") (pintype "passive"))
      (node (ref "U2") (pin "F4") (pinfunction "SLEEP_F4") (pintype "input"))
      (node (ref "U3") (pin "A1") (pinfunction "VSEL_A1") (pintype "passive"))
    )
    (net (code "35") (name "PWRKEY1") (class "Default")
      (node (ref "C53") (pin "1") (pinfunction "1_1") (pintype "passive"))
      (node (ref "R20") (pin "1") (pinfunction "1_1") (pintype "passive"))
      (node (ref "U2") (pin "E4") (pinfunction "PWRON_E4") (pintype "input"))
    )
    (net (code "36") (name "PWR_KEY") (class "Default")
      (node (ref "R19") (pin "1") (pinfunction "1_1") (pintype "passive"))
    )
    (net (code "37") (name "RESET") (class "Default")
      (node (ref "C57") (pin "1") (pinfunction "1_1") (pintype "passive"))
      (node (ref "R21") (pin "2") (pinfunction "2_2") (pintype "passive"))
      (node (ref "U2") (pin "F5") (pinfunction "RESETO_F5") (pintype "passive"))
    )
    (net (code "38") (name "RTC_CLKOUT1") (class "Default")
      (node (ref "U2") (pin "G7") (pinfunction "C32KOUT_G7") (pintype "output"))
    )
    (net (code "39") (name "RTC_CLKOUT2") (class "Default")
      (node (ref "R25") (pin "1") (pinfunction "1_1") (pintype "passive"))
    )
    (net (code "40") (name "VADP") (class "Default")
      (node (ref "C25") (pin "1") (pinfunction "1_1") (pintype "passive"))
      (node (ref "C32") (pin "2") (pinfunction "2_2") (pintype "passive"))
      (node (ref "C33") (pin "2") (pinfunction "2_2") (pintype "passive"))
      (node (ref "Q1") (pin "3") (pinfunction "DRAIN_3") (pintype "passive"))
      (node (ref "R6") (pin "1") (pinfunction "1_1") (pintype "passive"))
      (node (ref "R7") (pin "2") (pinfunction "2_2") (pintype "passive"))
      (node (ref "U2") (pin "A1") (pinfunction "VADP2_A1") (pintype "input"))
      (node (ref "U2") (pin "B1") (pinfunction "VADP1_B1") (pintype "input"))
      (node (ref "U2") (pin "D1") (pinfunction "VADPA_D1") (pintype "input"))
    )
    (net (code "41") (name "VCC18_DVP") (class "Default")
      (node (ref "C54") (pin "1") (pinfunction "1_1") (pintype "passive"))
      (node (ref "U4") (pin "1") (pinfunction "OUT2_1") (pintype "passive"))
    )
    (net (code "42") (name "VCC18_LCD") (class "Default")
      (node (ref "C39") (pin "1") (pinfunction "1_1") (pintype "passive"))
      (node (ref "U2") (pin "K3") (pinfunction "VOUT6_K3") (pintype "input"))
    )
    (net (code "43") (name "VCC28_DVP") (class "Default")
      (node (ref "C56") (pin "1") (pinfunction "1_1") (pintype "passive"))
      (node (ref "U4") (pin "6") (pinfunction "OUT1_6") (pintype "passive"))
    )
    (net (code "44") (name "VCC50_USB") (class "Default")
      (node (ref "Q1") (pin "2") (pinfunction "SOURCE_2") (pintype "passive"))
    )
    (net (code "45") (name "VCCA_CODEC") (class "Default")
      (node (ref "C46") (pin "1") (pinfunction "1_1") (pintype "passive"))
      (node (ref "U2") (pin "J5") (pinfunction "VOUT2_J5") (pintype "input"))
    )
    (net (code "46") (name "VCCIO_PMU") (class "Default")
      (node (ref "C45") (pin "1") (pinfunction "1_1") (pintype "passive"))
      (node (ref "C52") (pin "1") (pinfunction "1_1") (pintype "passive"))
      (node (ref "R21") (pin "1") (pinfunction "1_1") (pintype "passive"))
      (node (ref "R23") (pin "2") (pinfunction "2_2") (pintype "passive"))
      (node (ref "R24") (pin "2") (pinfunction "2_2") (pintype "passive"))
      (node (ref "U2") (pin "F6") (pinfunction "VDDIO_F6") (pintype "input"))
      (node (ref "U2") (pin "H4") (pinfunction "VOUT1_H4") (pintype "input"))
    )
    (net (code "47") (name "VCCIO_SD") (class "Default")
      (node (ref "C37") (pin "1") (pinfunction "1_1") (pintype "passive"))
      (node (ref "U2") (pin "K7") (pinfunction "VOUT8_K7") (pintype "input"))
    )
    (net (code "48") (name "VCC_18") (class "Default")
      (node (ref "C43") (pin "1") (pinfunction "1_1") (pintype "passive"))
      (node (ref "U2") (pin "J3") (pinfunction "VOUT10_J3") (pintype "input"))
    )
    (net (code "49") (name "VCC_20") (class "Default")
      (node (ref "C14") (pin "1") (pinfunction "1_1") (pintype "passive"))
      (node (ref "C15") (pin "1") (pinfunction "1_1") (pintype "passive"))
      (node (ref "C5") (pin "1") (pinfunction "1_1") (pintype "passive"))
      (node (ref "L4") (pin "2") (pinfunction "2_2") (pintype "passive"))
      (node (ref "U2") (pin "C7") (pinfunction "VFB2_C7") (pintype "input"))
      (node (ref "U2") (pin "G3") (pinfunction "VINL4_G3") (pintype "input"))
    )
    (net (code "50") (name "VCC_BAT+") (class "Default")
      (node (ref "C35") (pin "2") (pinfunction "2_2") (pintype "passive"))
      (node (ref "C41") (pin "1") (pinfunction "1_1") (pintype "passive"))
      (node (ref "J1") (pin "3") (pinfunction "3_3") (pintype "passive"))
      (node (ref "J1") (pin "4") (pinfunction "4_4") (pintype "passive"))
      (node (ref "P1") (pin "1") (pinfunction "1_1") (pintype "passive"))
      (node (ref "R12") (pin "2") (pinfunction "2_2") (pintype "passive"))
      (node (ref "U2") (pin "A6") (pinfunction "VBAT1_A6") (pintype "input"))
      (node (ref "U2") (pin "B6") (pinfunction "VBAT2_B6") (pintype "input"))
    )
    (net (code "51") (name "VCC_BAT-") (class "Default")
      (node (ref "J1") (pin "10") (pinfunction "10_10") (pintype "passive"))
      (node (ref "J1") (pin "9") (pinfunction "9_9") (pintype "passive"))
      (node (ref "P3") (pin "1") (pinfunction "1_1") (pintype "passive"))
      (node (ref "R17") (pin "2") (pinfunction "2_2") (pintype "passive"))
      (node (ref "U2") (pin "E3") (pinfunction "ICP_E3") (pintype "input"))
    )
    (net (code "52") (name "VCC_DDR") (class "Default")
      (node (ref "C26") (pin "1") (pinfunction "1_1") (pintype "passive"))
      (node (ref "C27") (pin "1") (pinfunction "1_1") (pintype "passive"))
      (node (ref "C28") (pin "1") (pinfunction "1_1") (pintype "passive"))
      (node (ref "L7") (pin "2") (pinfunction "2_2") (pintype "passive"))
      (node (ref "R10") (pin "1") (pinfunction "1_1") (pintype "passive"))
    )
    (net (code "53") (name "VCC_IO") (class "Default")
      (node (ref "C10") (pin "1") (pinfunction "1_1") (pintype "passive"))
      (node (ref "C11") (pin "1") (pinfunction "1_1") (pintype "passive"))
      (node (ref "C18") (pin "1") (pinfunction "1_1") (pintype "passive"))
      (node (ref "C55") (pin "1") (pinfunction "1_1") (pintype "passive"))
      (node (ref "L3") (pin "2") (pinfunction "2_2") (pintype "passive"))
      (node (ref "U2") (pin "C6") (pinfunction "VFB1_C6") (pintype "input"))
      (node (ref "U2") (pin "H5") (pinfunction "VINL2_H5") (pintype "input"))
      (node (ref "U4") (pin "5") (pinfunction "VIN_5") (pintype "passive"))
    )
    (net (code "54") (name "VCC_LCD") (class "Default")
      (node (ref "C20") (pin "1") (pinfunction "1_1") (pintype "passive"))
      (node (ref "C21") (pin "1") (pinfunction "1_1") (pintype "passive"))
      (node (ref "L5") (pin "2") (pinfunction "2_2") (pintype "passive"))
      (node (ref "U2") (pin "D7") (pinfunction "VFB3_D7") (pintype "input"))
    )
    (net (code "55") (name "VCC_RTC") (class "Default")
      (node (ref "C47") (pin "1") (pinfunction "1_1") (pintype "passive"))
      (node (ref "U2") (pin "J7") (pinfunction "VSB_J7") (pintype "input"))
    )
    (net (code "56") (name "VCC_SD") (class "Default")
      (node (ref "C30") (pin "1") (pinfunction "1_1") (pintype "passive"))
      (node (ref "U2") (pin "J4") (pinfunction "VOUT4_J4") (pintype "input"))
    )
    (net (code "57") (name "VCC_SYS") (class "Default")
      (node (ref "C1") (pin "1") (pinfunction "1_1") (pintype "passive"))
      (node (ref "C12") (pin "1") (pinfunction "1_1") (pintype "passive"))
      (node (ref "C13") (pin "1") (pinfunction "1_1") (pintype "passive"))
      (node (ref "C16") (pin "1") (pinfunction "1_1") (pintype "passive"))
      (node (ref "C17") (pin "1") (pinfunction "1_1") (pintype "passive"))
      (node (ref "C19") (pin "1") (pinfunction "1_1") (pintype "passive"))
      (node (ref "C38") (pin "1") (pinfunction "1_1") (pintype "passive"))
      (node (ref "C6") (pin "1") (pinfunction "1_1") (pintype "passive"))
      (node (ref "C8") (pin "1") (pinfunction "1_1") (pintype "passive"))
      (node (ref "C9") (pin "1") (pinfunction "1_1") (pintype "passive"))
      (node (ref "R11") (pin "1") (pinfunction "1_1") (pintype "passive"))
      (node (ref "R20") (pin "2") (pinfunction "2_2") (pintype "passive"))
      (node (ref "U1") (pin "D1") (pinfunction "VIN_D1") (pintype "power_in"))
      (node (ref "U1") (pin "D2") (pinfunction "VIN_D2") (pintype "power_in"))
      (node (ref "U1") (pin "E1") (pinfunction "VIN_E1") (pintype "power_in"))
      (node (ref "U1") (pin "E2") (pinfunction "VIN_E2") (pintype "power_in"))
      (node (ref "U2") (pin "A5") (pinfunction "VSYS1_A5") (pintype "input"))
      (node (ref "U2") (pin "A7") (pinfunction "VINP1_A7") (pintype "input"))
      (node (ref "U2") (pin "B5") (pinfunction "VSYS2_B5") (pintype "input"))
      (node (ref "U2") (pin "B8") (pinfunction "VINP2_B8") (pintype "input"))
      (node (ref "U2") (pin "C5") (pinfunction "ILM_C5") (pintype "input"))
      (node (ref "U2") (pin "E1") (pinfunction "VINP4_E1") (pintype "input"))
      (node (ref "U2") (pin "G4") (pinfunction "VINL3_G4") (pintype "input"))
      (node (ref "U2") (pin "G5") (pinfunction "VINL1_G5") (pintype "input"))
      (node (ref "U2") (pin "G8") (pinfunction "VINP3_G8") (pintype "input"))
      (node (ref "U2") (pin "K2") (pinfunction "VINP5_K2") (pintype "input"))
      (node (ref "U3") (pin "D1") (pinfunction "VIN_D1") (pintype "power_in"))
      (node (ref "U3") (pin "D2") (pinfunction "VIN_D2") (pintype "power_in"))
      (node (ref "U3") (pin "E1") (pinfunction "VIN_E1") (pintype "power_in"))
      (node (ref "U3") (pin "E2") (pinfunction "VIN_E2") (pintype "power_in"))
    )
    (net (code "58") (name "VCC_TP") (class "Default")
      (node (ref "C29") (pin "1") (pinfunction "1_1") (pintype "passive"))
      (node (ref "U2") (pin "K4") (pinfunction "VOUT3_K4") (pintype "input"))
    )
    (net (code "59") (name "VCC_USBPWR") (class "Default")
      (node (ref "Q1") (pin "1") (pinfunction "GATE_1") (pintype "input"))
      (node (ref "R13") (pin "2") (pinfunction "2_2") (pintype "passive"))
    )
    (net (code "60") (name "VCC_WL") (class "Default")
      (node (ref "C34") (pin "1") (pinfunction "1_1") (pintype "passive"))
      (node (ref "U2") (pin "K5") (pinfunction "VOUT5_K5") (pintype "input"))
    )
    (net (code "61") (name "VDD10_LCD") (class "Default")
      (node (ref "C36") (pin "1") (pinfunction "1_1") (pintype "passive"))
      (node (ref "U2") (pin "H6") (pinfunction "VOUT7_H6") (pintype "input"))
    )
    (net (code "62") (name "VDD_10") (class "Default")
      (node (ref "C42") (pin "1") (pinfunction "1_1") (pintype "passive"))
      (node (ref "U2") (pin "H3") (pinfunction "VOUT9_H3") (pintype "input"))
    )
    (net (code "63") (name "VDD_CPU") (class "Default")
      (node (ref "C4") (pin "1") (pinfunction "1_1") (pintype "passive"))
      (node (ref "C7") (pin "1") (pinfunction "1_1") (pintype "passive"))
      (node (ref "L2") (pin "2") (pinfunction "2_2") (pintype "passive"))
      (node (ref "R3") (pin "1") (pinfunction "1_1") (pintype "passive"))
    )
    (net (code "64") (name "VDD_CPU_FB") (class "Default")
      (node (ref "R3") (pin "2") (pinfunction "2_2") (pintype "passive"))
      (node (ref "U3") (pin "A4") (pinfunction "VOUT_A4") (pintype "passive"))
    )
    (net (code "65") (name "VDD_GPU") (class "Default")
      (node (ref "C2") (pin "1") (pinfunction "1_1") (pintype "passive"))
      (node (ref "C3") (pin "1") (pinfunction "1_1") (pintype "passive"))
      (node (ref "L1") (pin "2") (pinfunction "2_2") (pintype "passive"))
      (node (ref "R1") (pin "1") (pinfunction "1_1") (pintype "passive"))
    )
    (net (code "66") (name "VDD_GPU_FB") (class "Default")
      (node (ref "R1") (pin "2") (pinfunction "2_2") (pintype "passive"))
      (node (ref "U1") (pin "A4") (pinfunction "VOUT_A4") (pintype "passive"))
    )
    (net (code "67") (name "VDD_LOG") (class "Default")
      (node (ref "C23") (pin "1") (pinfunction "1_1") (pintype "passive"))
      (node (ref "C24") (pin "1") (pinfunction "1_1") (pintype "passive"))
      (node (ref "L6") (pin "2") (pinfunction "2_2") (pintype "passive"))
      (node (ref "U2") (pin "E2") (pinfunction "VFB4_E2") (pintype "input"))
    )
    (net (code "68") (name "unconnected-(J1-Pad5)") (class "Default")
      (node (ref "J1") (pin "5") (pinfunction "5_5") (pintype "passive"))
    )
    (net (code "69") (name "unconnected-(J1-Pad6)") (class "Default")
      (node (ref "J1") (pin "6") (pinfunction "6_6") (pintype "passive"))
    )
    (net (code "70") (name "unconnected-(J1-Pad8)") (class "Default")
      (node (ref "J1") (pin "8") (pinfunction "8_8") (pintype "passive"))
    )
  )
)
